# schematic_2.net
KiCad netlist of a schematic drawn in EAGLE
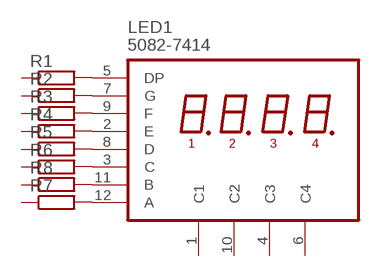
[diagram p0: schematic, sheet 1]

(export (version "E")
  (design (tool "Eeschema 10.0.6"))
  (components
    (comp (ref "LED1")
      (value "5082-7414")
      (footprint "eagle-import:5082-7414")
      (libsource (lib "eagle-import") (part "5082-7414"))
    )
    (comp (ref "R1")
      (value "R-EU_0204/2V")
      (footprint "eagle-import:0204V")
      (libsource (lib "eagle-import") (part "R-EU_0204/2V"))
    )
    (comp (ref "R2")
      (value "R-EU_0204/2V")
      (footprint "eagle-import:0204V")
      (libsource (lib "eagle-import") (part "R-EU_0204/2V"))
    )
    (comp (ref "R3")
      (value "R-EU_0204/2V")
      (footprint "eagle-import:0204V")
      (libsource (lib "eagle-import") (part "R-EU_0204/2V"))
    )
    (comp (ref "R4")
      (value "R-EU_0204/2V")
      (footprint "eagle-import:0204V")
      (libsource (lib "eagle-import") (part "R-EU_0204/2V"))
    )
    (comp (ref "R5")
      (value "R-EU_0204/2V")
      (footprint "eagle-import:0204V")
      (libsource (lib "eagle-import") (part "R-EU_0204/2V"))
    )
    (comp (ref "R6")
      (value "R-EU_0204/2V")
      (footprint "eagle-import:0204V")
      (libsource (lib "eagle-import") (part "R-EU_0204/2V"))
    )
    (comp (ref "R7")
      (value "R-EU_0204/2V")
      (footprint "eagle-import:0204V")
      (libsource (lib "eagle-import") (part "R-EU_0204/2V"))
    )
    (comp (ref "R8")
      (value "R-EU_0204/2V")
      (footprint "eagle-import:0204V")
      (libsource (lib "eagle-import") (part "R-EU_0204/2V"))
    )
  )
  (nets
    (net (code "1") (name "Net-(LED1-A)") (class "Default")
      (node (ref "LED1") (pin "12") (pinfunction "A_12") (pintype "passive"))
      (node (ref "R7") (pin "2") (pinfunction "2_2") (pintype "passive"))
    )
    (net (code "2") (name "Net-(LED1-B)") (class "Default")
      (node (ref "LED1") (pin "11") (pinfunction "B_11") (pintype "passive"))
      (node (ref "R8") (pin "2") (pinfunction "2_2") (pintype "passive"))
    )
    (net (code "3") (name "Net-(LED1-C)") (class "Default")
      (node (ref "LED1") (pin "3") (pinfunction "C_3") (pintype "passive"))
      (node (ref "R6") (pin "2") (pinfunction "2_2") (pintype "passive"))
    )
    (net (code "4") (name "Net-(LED1-D)") (class "Default")
      (node (ref "LED1") (pin "8") (pinfunction "D_8") (pintype "passive"))
      (node (ref "R5") (pin "2") (pinfunction "2_2") (pintype "passive"))
    )
    (net (code "5") (name "Net-(LED1-DP)") (class "Default")
      (node (ref "LED1") (pin "5") (pinfunction "DP_5") (pintype "passive"))
      (node (ref "R1") (pin "2") (pinfunction "2_2") (pintype "passive"))
    )
    (net (code "6") (name "Net-(LED1-E)") (class "Default")
      (node (ref "LED1") (pin "2") (pinfunction "E_2") (pintype "passive"))
      (node (ref "R4") (pin "2") (pinfunction "2_2") (pintype "passive"))
    )
    (net (code "7") (name "Net-(LED1-F)") (class "Default")
      (node (ref "LED1") (pin "9") (pinfunction "F_9") (pintype "passive"))
      (node (ref "R3") (pin "2") (pinfunction "2_2") (pintype "passive"))
    )
    (net (code "8") (name "Net-(LED1-G)") (class "Default")
      (node (ref "LED1") (pin "7") (pinfunction "G_7") (pintype "passive"))
      (node (ref "R2") (pin "2") (pinfunction "2_2") (pintype "passive"))
    )
    (net (code "9") (name "unconnected-(LED1-C1-Pad1)") (class "Default")
      (node (ref "LED1") (pin "1") (pinfunction "C1_1") (pintype "passive"))
    )
    (net (code "10") (name "unconnected-(LED1-C2-Pad10)") (class "Default")
      (node (ref "LED1") (pin "10") (pinfunction "C2_10") (pintype "passive"))
    )
    (net (code "11") (name "unconnected-(LED1-C3-Pad4)") (class "Default")
      (node (ref "LED1") (pin "4") (pinfunction "C3_4") (pintype "passive"))
    )
    (net (code "12") (name "unconnected-(LED1-C4-Pad6)") (class "Default")
      (node (ref "LED1") (pin "6") (pinfunction "C4_6") (pintype "no_connect"))
    )
    (net (code "13") (name "unconnected-(R1-Pad1)") (class "Default")
      (node (ref "R1") (pin "1") (pinfunction "1_1") (pintype "passive"))
    )
    (net (code "14") (name "unconnected-(R2-Pad1)") (class "Default")
      (node (ref "R2") (pin "1") (pinfunction "1_1") (pintype "passive"))
    )
    (net (code "15") (name "unconnected-(R3-Pad1)") (class "Default")
      (node (ref "R3") (pin "1") (pinfunction "1_1") (pintype "passive"))
    )
    (net (code "16") (name "unconnected-(R4-Pad1)") (class "Default")
      (node (ref "R4") (pin "1") (pinfunction "1_1") (pintype "passive"))
    )
    (net (code "17") (name "unconnected-(R5-Pad1)") (class "Default")
      (node (ref "R5") (pin "1") (pinfunction "1_1") (pintype "passive"))
    )
    (net (code "18") (name "unconnected-(R6-Pad1)") (class "Default")
      (node (ref "R6") (pin "1") (pinfunction "1_1") (pintype "passive"))
    )
    (net (code "19") (name "unconnected-(R7-Pad1)") (class "Default")
      (node (ref "R7") (pin "1") (pinfunction "1_1") (pintype "passive"))
    )
    (net (code "20") (name "unconnected-(R8-Pad1)") (class "Default")
      (node (ref "R8") (pin "1") (pinfunction "1_1") (pintype "passive"))
    )
  )
)
